# 2_DS3231.net
KiCad netlist of a schematic drawn in Altium Designer
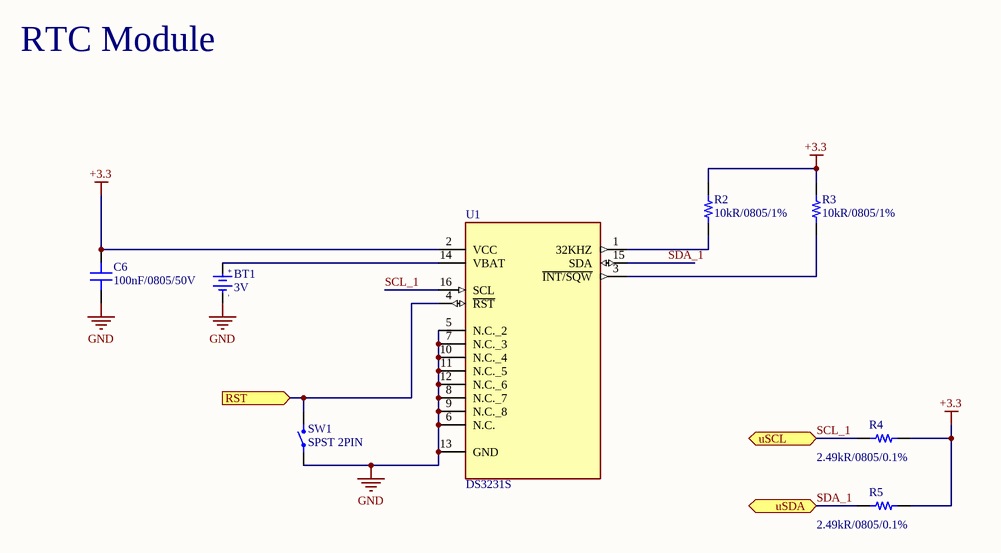
[diagram p0: 2_DS3231.SchDoc]

(export (version "E")
  (design (tool "Eeschema 10.0.6"))
  (components
    (comp (ref "BT1")
      (value "3V")
      (footprint "PIN3V")
      (description "Battery 3VDC")
      (libsource (lib "LIBRARYALT") (part "PIN 3V"))
    )
    (comp (ref "C6")
      (value "100nF/0805/50V")
      (footprint "CAP FILM 0805")
      (description "Multilayer Ceramic Capacitor, 0.1 uF, 50 V, ï¿½ 10%, X7R, 0805 [2012 Metric]")
      (fields
        (field (name "MANUFACTURER") "Samsung")
        (field (name "MANUFACTURER PART NUMBER") "CL21B104KBCNNNC")
      )
      (libsource (lib "NLOC_Altium_Library") (part "Capacitor - MLCC"))
    )
    (comp (ref "R2")
      (value "10kR/0805/1%")
      (footprint "RES 0805_2012")
      (description "SMD Chip Resistor, 10 kOhm, ï¿½ 1%, 125 mW, 0805 [2012 Metric], Thick Film, General Purpose")
      (fields
        (field (name "MANUFACTURER") "Yageo")
        (field (name "MANUFACTURER PART NUMBER") "RC0805FR-0710KL")
      )
      (libsource (lib "NLOC_Altium_Library") (part "Resistor"))
    )
    (comp (ref "R3")
      (value "10kR/0805/1%")
      (footprint "RES 0805_2012")
      (description "SMD Chip Resistor, 10 kOhm, ï¿½ 1%, 125 mW, 0805 [2012 Metric], Thick Film, General Purpose")
      (fields
        (field (name "MANUFACTURER") "Yageo")
        (field (name "MANUFACTURER PART NUMBER") "RC0805FR-0710KL")
      )
      (libsource (lib "NLOC_Altium_Library") (part "Resistor"))
    )
    (comp (ref "R4")
      (value "2.49kR/0805/0.1%")
      (footprint "RES 0805_2012")
      (description "SMD Chip Resistor, High Precision, 2.49 kohm, ± 0.1%, 250 mW, 0805 [2012 Metric], Thick Film")
      (fields
        (field (name "MANUFACTURER") "Panasonic")
        (field (name "MANUFACTURER PART NUMBER") "ERJ-PB6B2491V")
      )
      (libsource (lib "NLOC_Altium_Library") (part "Resistor"))
    )
    (comp (ref "R5")
      (value "2.49kR/0805/0.1%")
      (footprint "RES 0805_2012")
      (description "SMD Chip Resistor, High Precision, 2.49 kohm, ± 0.1%, 250 mW, 0805 [2012 Metric], Thick Film")
      (fields
        (field (name "MANUFACTURER") "Panasonic")
        (field (name "MANUFACTURER PART NUMBER") "ERJ-PB6B2491V")
      )
      (libsource (lib "NLOC_Altium_Library") (part "Resistor"))
    )
    (comp (ref "SW1")
      (value "SPST 2PIN")
      (footprint "3x4 SPST BUTTON")
      (libsource (lib "NLOC_Altium_Library") (part "SPST 2PIN"))
    )
    (comp (ref "U1")
      (value "DS3231S")
      (footprint "SOIC127P1032X265-16N")
      (description "Real Time Clock (RTC) IC Clock/Calendar - IÂ²C, 2-Wire Serial 16-SOIC (0.295, 7.50mm Width)")
      (fields (field (name "MF") "Maxim Integrated") (field (name "MP") "DS3231S#"))
      (libsource (lib "DS3231S") (part "DS3231S"))
    )
  )
  (nets
    (net (code "1") (name "+3.3") (class "Default")
      (node (ref "C6") (pin "2") (pinfunction "2_2") (pintype "passive"))
      (node (ref "R2") (pin "2") (pinfunction "2_2") (pintype "passive"))
      (node (ref "R3") (pin "2") (pinfunction "2_2") (pintype "passive"))
      (node (ref "R4") (pin "1") (pinfunction "1_1") (pintype "passive"))
      (node (ref "R5") (pin "1") (pinfunction "1_1") (pintype "passive"))
      (node (ref "U1") (pin "2") (pinfunction "VCC_2") (pintype "power_in"))
    )
    (net (code "2") (name "/RST") (class "Default")
      (node (ref "SW1") (pin "2") (pinfunction "2_2") (pintype "passive"))
      (node (ref "U1") (pin "4") (pinfunction "~{RST}_4") (pintype "bidirectional"))
    )
    (net (code "3") (name "/SCL_1") (class "Default")
      (node (ref "R4") (pin "2") (pinfunction "2_2") (pintype "passive"))
      (node (ref "U1") (pin "16") (pinfunction "SCL_16") (pintype "input"))
    )
    (net (code "4") (name "/SDA_1") (class "Default")
      (node (ref "R5") (pin "2") (pinfunction "2_2") (pintype "passive"))
      (node (ref "U1") (pin "15") (pinfunction "SDA_15") (pintype "bidirectional"))
    )
    (net (code "5") (name "GND") (class "Default")
      (node (ref "BT1") (pin "2") (pinfunction "GND_2") (pintype "passive"))
      (node (ref "C6") (pin "1") (pinfunction "1_1") (pintype "passive"))
      (node (ref "SW1") (pin "1") (pinfunction "1_1") (pintype "passive"))
      (node (ref "U1") (pin "10") (pinfunction "N.C._4_10") (pintype "passive"))
      (node (ref "U1") (pin "11") (pinfunction "N.C._5_11") (pintype "passive"))
      (node (ref "U1") (pin "12") (pinfunction "N.C._6_12") (pintype "passive"))
      (node (ref "U1") (pin "13") (pinfunction "GND_13") (pintype "passive"))
      (node (ref "U1") (pin "5") (pinfunction "N.C._2_5") (pintype "passive"))
      (node (ref "U1") (pin "6") (pinfunction "N.C._6") (pintype "passive"))
      (node (ref "U1") (pin "7") (pinfunction "N.C._3_7") (pintype "passive"))
      (node (ref "U1") (pin "8") (pinfunction "N.C._7_8") (pintype "passive"))
      (node (ref "U1") (pin "9") (pinfunction "N.C._8_9") (pintype "passive"))
    )
    (net (code "6") (name "Net-(BT1-+3V)") (class "Default")
      (node (ref "BT1") (pin "1") (pinfunction "+3V_1") (pintype "passive"))
      (node (ref "U1") (pin "14") (pinfunction "VBAT_14") (pintype "power_in"))
    )
    (net (code "7") (name "Net-(U1-32KHZ)") (class "Default")
      (node (ref "R2") (pin "1") (pinfunction "1_1") (pintype "passive"))
      (node (ref "U1") (pin "1") (pinfunction "32KHZ_1") (pintype "output"))
    )
    (net (code "8") (name "Net-(U1-~{INT{slash}SQW})") (class "Default")
      (node (ref "R3") (pin "1") (pinfunction "1_1") (pintype "passive"))
      (node (ref "U1") (pin "3") (pinfunction "~{INT/SQW}_3") (pintype "output"))
    )
  )
)
